# USBINFRTransiever_Photodiod.net
KiCad netlist of a schematic drawn in Altium Designer
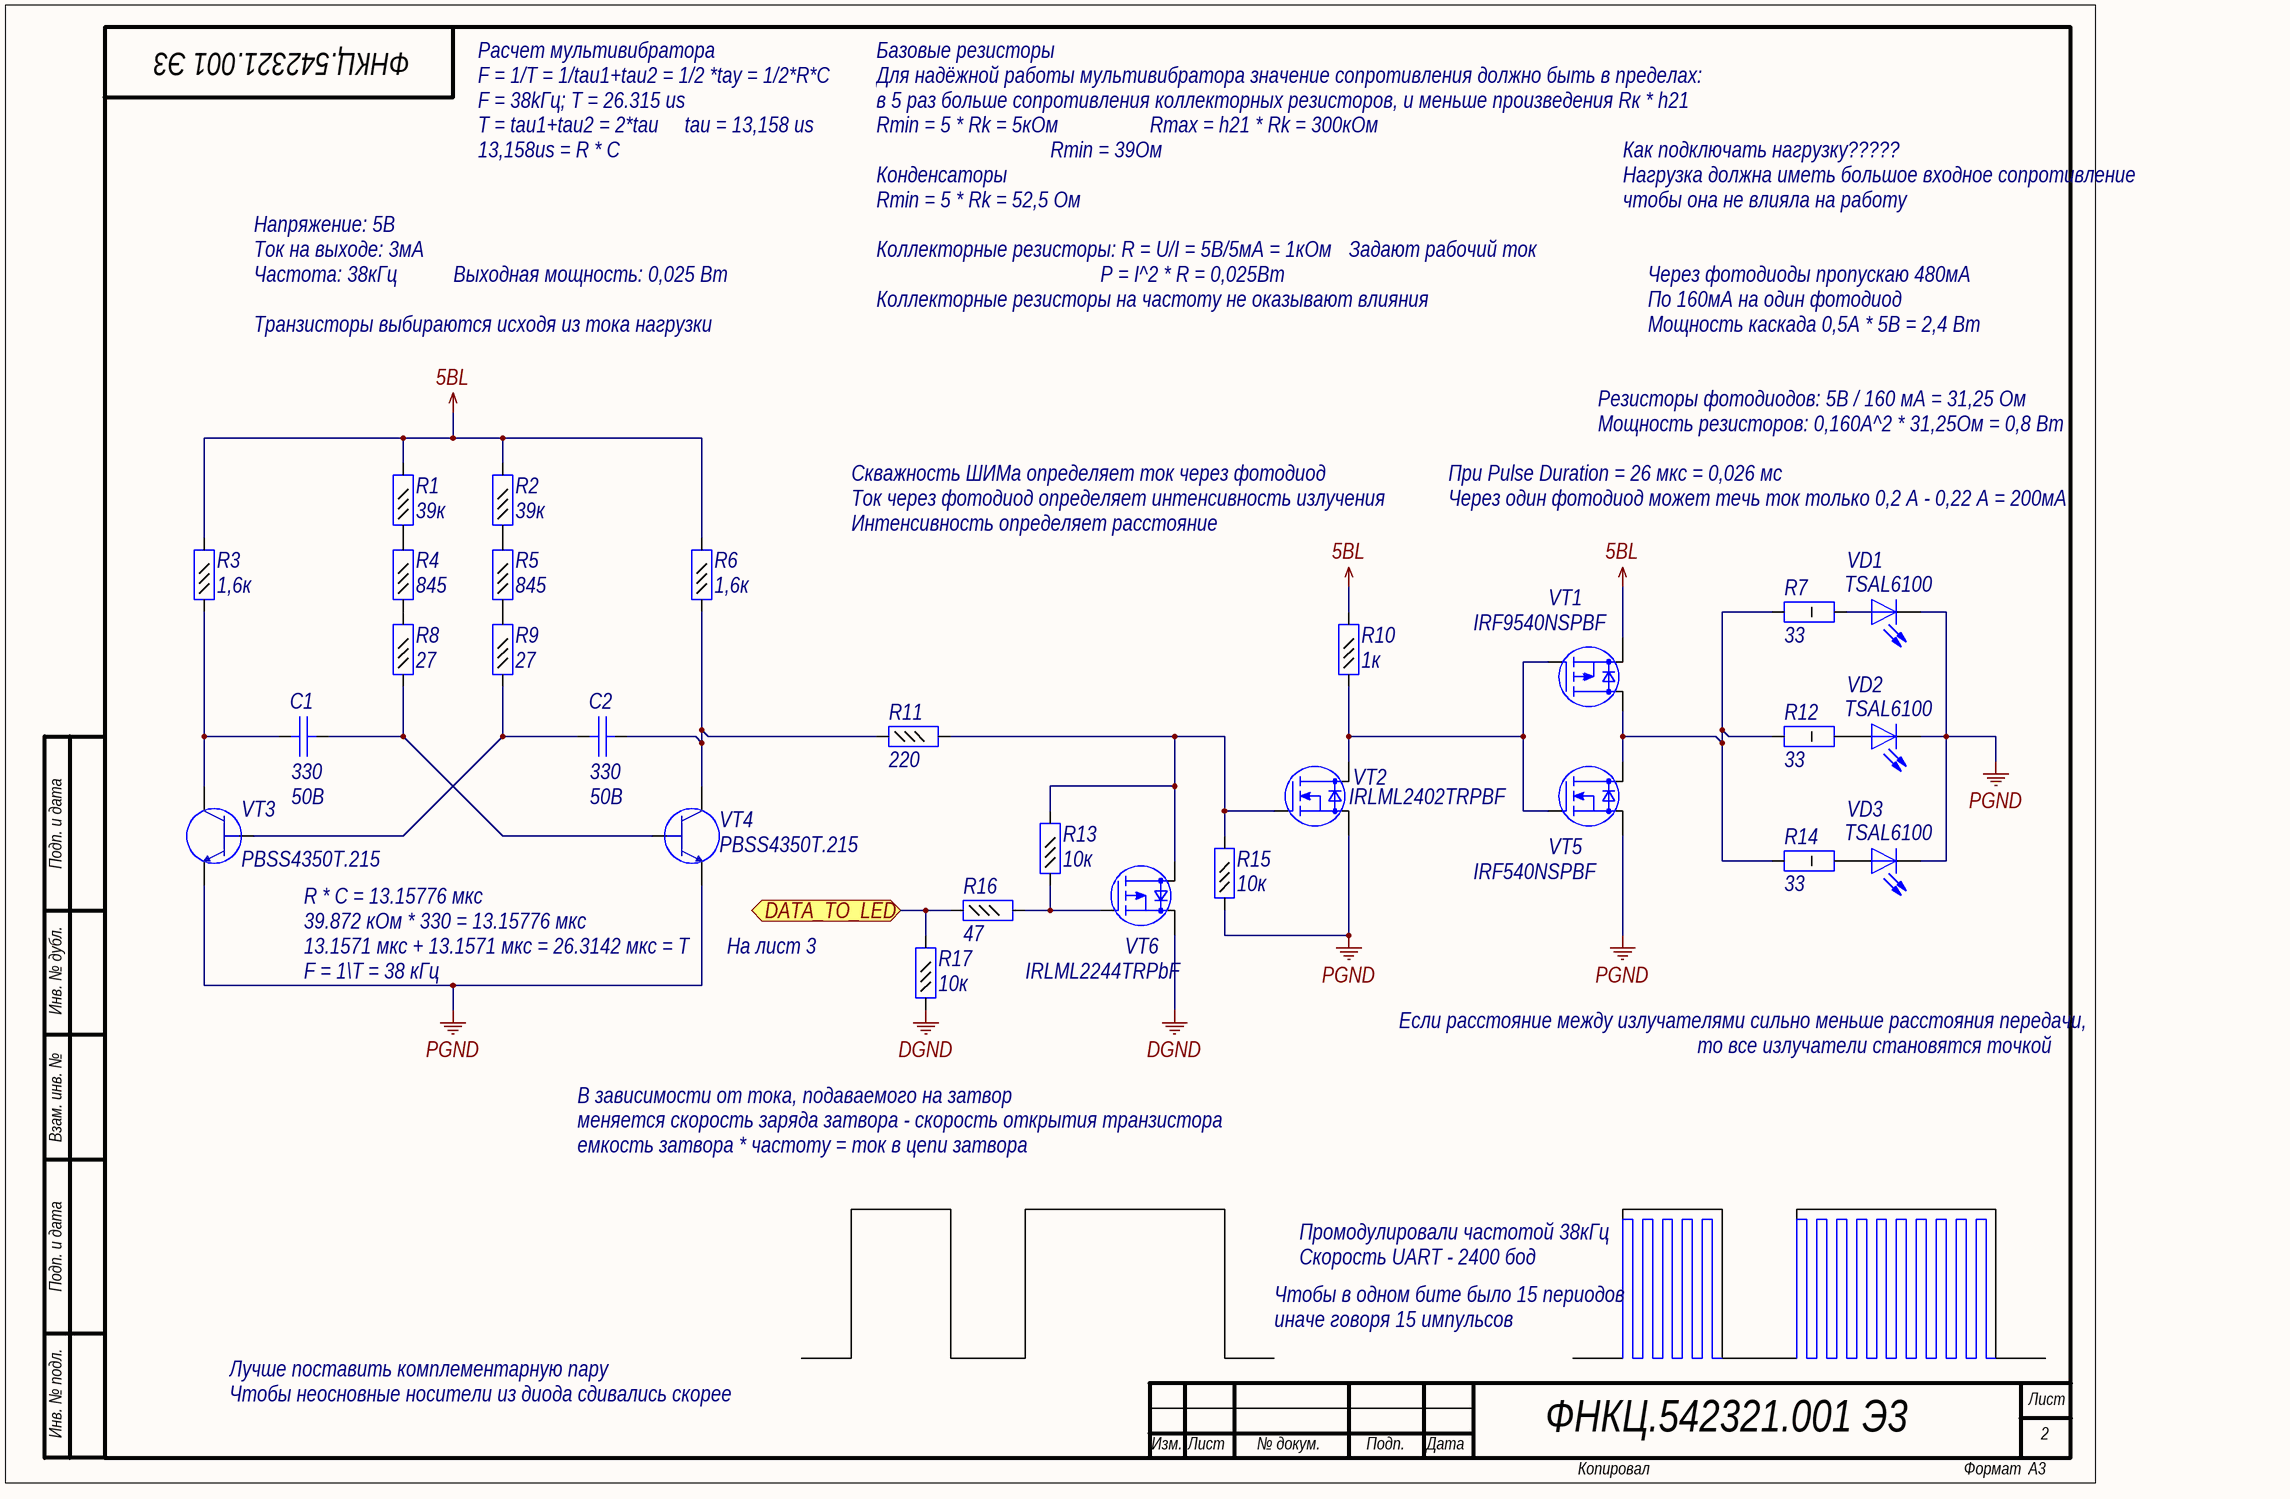
[diagram p0: USBINFRTransiever_Photodiod.SchDoc]

(export (version "E")
  (design (tool "Eeschema 10.0.6"))
  (components
    (comp (ref "C1")
      (value "330")
      (footprint "C0603")
      (description "Конденсатор")
      (fields
        (field (name "VOLTAGE") "50В")
        (field (name "PART NUMBER") "GRM188R71H331KA01D")
        (field (name "Comment") "Capacitor")
      )
      (libsource (lib "MOP44") (part "Capacitor"))
    )
    (comp (ref "C2")
      (value "330")
      (footprint "C0603")
      (description "Конденсатор")
      (fields
        (field (name "VOLTAGE") "50В")
        (field (name "PART NUMBER") "GRM188R71H331KA01D")
        (field (name "Comment") "Capacitor")
      )
      (libsource (lib "MOP44") (part "Capacitor"))
    )
    (comp (ref "R1")
      (value "39к")
      (footprint "R0603")
      (description "Резистор")
      (fields (field (name "PART NUMBER") "RC0603FR-0739KL") (field (name "POWER") "0,062Вт"))
      (libsource (lib "") (part "Resistor_0,062Вт_1"))
    )
    (comp (ref "R2")
      (value "39к")
      (footprint "R0603")
      (description "Резистор")
      (fields (field (name "PART NUMBER") "RC0603FR-0739KL") (field (name "POWER") "0,062Вт"))
      (libsource (lib "") (part "Resistor_0,062Вт_1"))
    )
    (comp (ref "R3")
      (value "1,6к")
      (footprint "R0603")
      (description "Резистор")
      (fields (field (name "PART NUMBER") "RC0603FR-071K6") (field (name "POWER") "0,062Вт"))
      (libsource (lib "") (part "Resistor_0,062Вт_1"))
    )
    (comp (ref "R4")
      (value "845")
      (footprint "R0603")
      (description "Резистор")
      (fields (field (name "PART NUMBER") "RC0603FR-07845RL") (field (name "POWER") "0,062Вт"))
      (libsource (lib "") (part "Resistor_0,062Вт_1"))
    )
    (comp (ref "R5")
      (value "845")
      (footprint "R0603")
      (description "Резистор")
      (fields (field (name "PART NUMBER") "RC0603FR-07845RL") (field (name "POWER") "0,062Вт"))
      (libsource (lib "") (part "Resistor_0,062Вт_1"))
    )
    (comp (ref "R6")
      (value "1,6к")
      (footprint "R0603")
      (description "Резистор")
      (fields (field (name "PART NUMBER") "RC0603FR-071K6") (field (name "POWER") "0,062Вт"))
      (libsource (lib "") (part "Resistor_0,062Вт_1"))
    )
    (comp (ref "R7")
      (value "33")
      (footprint "R2512")
      (description "Резистор")
      (fields (field (name "PART NUMBER") "RC2512FR-0733RL") (field (name "POWER") "1Вт"))
      (libsource (lib "MOP44") (part "Resistor_1Вт"))
    )
    (comp (ref "R8")
      (value "27")
      (footprint "R0603")
      (description "Резистор")
      (fields (field (name "PART NUMBER") "RC0603FR-0727RL") (field (name "POWER") "0,062Вт"))
      (libsource (lib "") (part "Resistor_0,062Вт_1"))
    )
    (comp (ref "R9")
      (value "27")
      (footprint "R0603")
      (description "Резистор")
      (fields (field (name "PART NUMBER") "RC0603FR-0727RL") (field (name "POWER") "0,062Вт"))
      (libsource (lib "") (part "Resistor_0,062Вт_1"))
    )
    (comp (ref "R10")
      (value "1к")
      (footprint "R0603")
      (description "Резистор")
      (fields (field (name "PART NUMBER") "RC0603FR-071KL") (field (name "POWER") "0,062Вт"))
      (libsource (lib "") (part "Resistor_0,062Вт_1"))
    )
    (comp (ref "R11")
      (value "220")
      (footprint "R0603")
      (description "Резистор")
      (fields (field (name "PART NUMBER") "RC0603FR-07220RL") (field (name "POWER") "0,062Вт"))
      (libsource (lib "MOP44") (part "Resistor_0,062Вт"))
    )
    (comp (ref "R12")
      (value "33")
      (footprint "R2512")
      (description "Резистор")
      (fields (field (name "PART NUMBER") "RC2512FR-0733RL") (field (name "POWER") "1Вт"))
      (libsource (lib "MOP44") (part "Resistor_1Вт"))
    )
    (comp (ref "R13")
      (value "10к")
      (footprint "R0603")
      (description "Резистор")
      (fields (field (name "PART NUMBER") "RC0603FR-0710KL") (field (name "POWER") "0,062Вт"))
      (libsource (lib "") (part "Resistor_0,062Вт_1"))
    )
    (comp (ref "R14")
      (value "33")
      (footprint "R2512")
      (description "Резистор")
      (fields (field (name "PART NUMBER") "RC2512FR-0733RL") (field (name "POWER") "1Вт"))
      (libsource (lib "MOP44") (part "Resistor_1Вт"))
    )
    (comp (ref "R15")
      (value "10к")
      (footprint "R0603")
      (description "Резистор")
      (fields (field (name "PART NUMBER") "RC0603FR-0710KL") (field (name "POWER") "0,062Вт"))
      (libsource (lib "") (part "Resistor_0,062Вт_1"))
    )
    (comp (ref "R16")
      (value "47")
      (footprint "R0603")
      (description "Резистор")
      (fields (field (name "PART NUMBER") "RC0603FR-0747RL") (field (name "POWER") "0,062Вт"))
      (libsource (lib "MOP44") (part "Resistor_0,062Вт"))
    )
    (comp (ref "R17")
      (value "10к")
      (footprint "R0603")
      (description "Резистор")
      (fields (field (name "PART NUMBER") "RC0603FR-0710KL") (field (name "POWER") "0,062Вт"))
      (libsource (lib "") (part "Resistor_0,062Вт_1"))
    )
    (comp (ref "VD1")
      (value "LED")
      (footprint "RADIAL_5MM")
      (description "Светодиод")
      (fields (field (name "PART NUMBER") "TSAL6100"))
      (libsource (lib "MOP44") (part "LED"))
    )
    (comp (ref "VD2")
      (value "LED")
      (footprint "RADIAL_5MM")
      (description "Светодиод")
      (fields (field (name "PART NUMBER") "TSAL6100"))
      (libsource (lib "MOP44") (part "LED"))
    )
    (comp (ref "VD3")
      (value "LED")
      (footprint "RADIAL_5MM")
      (description "Светодиод")
      (fields (field (name "PART NUMBER") "TSAL6100"))
      (libsource (lib "MOP44") (part "LED"))
    )
    (comp (ref "VT1")
      (value "P-MOSFET")
      (footprint "D2PAK")
      (description "N-MOSFET")
      (fields
        (field (name "PART NUMBER") "IRF9540NSPBF")
        (field (name "MANUFACTURER") "International Rectifier")
      )
      (libsource (lib "MOP44") (part "P-MOSFET"))
    )
    (comp (ref "VT2")
      (value "N-MOSFET")
      (footprint "SOT23-3")
      (fields
        (field (name "PART NUMBER") "IRLML2402TRPBF")
        (field (name "MANUFACTURER") "International Rectifier")
      )
      (libsource (lib "MOP44") (part "N-MOSFET"))
    )
    (comp (ref "VT3")
      (value "BJT NPN")
      (footprint "SOT23-3")
      (fields (field (name "POWER") "0,48Вт") (field (name "PART NUMBER") "PBSS4350T.215"))
      (libsource (lib "MOP44") (part "BJT NPN"))
    )
    (comp (ref "VT4")
      (value "BJT NPN")
      (footprint "SOT23-3")
      (fields (field (name "POWER") "0,48Вт") (field (name "PART NUMBER") "PBSS4350T.215"))
      (libsource (lib "MOP44") (part "BJT NPN"))
    )
    (comp (ref "VT5")
      (value "N-MOSFET")
      (footprint "D2PAK")
      (fields
        (field (name "PART NUMBER") "IRF540NSPBF")
        (field (name "MANUFACTURER") "International Rectifier")
      )
      (libsource (lib "MOP44") (part "N-MOSFET"))
    )
    (comp (ref "VT6")
      (value "P-MOSFET")
      (footprint "SOT23-3")
      (description "N-MOSFET")
      (fields
        (field (name "PART NUMBER") "IRLML2244TRPbF")
        (field (name "MANUFACTURER") "International Rectifier")
      )
      (libsource (lib "MOP44") (part "P-MOSFET"))
    )
  )
  (nets
    (net (code "1") (name "/DATA_TO_LED") (class "Default")
      (node (ref "R16") (pin "1") (pinfunction "1_1") (pintype "passive"))
      (node (ref "R17") (pin "2") (pinfunction "2_2") (pintype "passive"))
    )
    (net (code "2") (name "5ВL") (class "Default")
      (node (ref "R1") (pin "2") (pinfunction "2_2") (pintype "passive"))
      (node (ref "R10") (pin "2") (pinfunction "2_2") (pintype "passive"))
      (node (ref "R2") (pin "2") (pinfunction "2_2") (pintype "passive"))
      (node (ref "R3") (pin "2") (pinfunction "2_2") (pintype "passive"))
      (node (ref "R6") (pin "2") (pinfunction "2_2") (pintype "passive"))
      (node (ref "VT1") (pin "2") (pinfunction "S_2") (pintype "passive"))
    )
    (net (code "3") (name "DGND") (class "Default")
      (node (ref "R17") (pin "1") (pinfunction "1_1") (pintype "passive"))
      (node (ref "VT6") (pin "2") (pinfunction "S_2") (pintype "passive"))
    )
    (net (code "4") (name "Net-(C1-Pad1)") (class "Default")
      (node (ref "C1") (pin "1") (pinfunction "1_1") (pintype "passive"))
      (node (ref "R3") (pin "1") (pinfunction "1_1") (pintype "passive"))
      (node (ref "VT3") (pin "3") (pinfunction "3_3") (pintype "passive"))
    )
    (net (code "5") (name "Net-(C1-Pad2)") (class "Default")
      (node (ref "C1") (pin "2") (pinfunction "2_2") (pintype "passive"))
      (node (ref "R8") (pin "1") (pinfunction "1_1") (pintype "passive"))
      (node (ref "VT4") (pin "1") (pinfunction "1_1") (pintype "passive"))
    )
    (net (code "6") (name "Net-(C2-Pad1)") (class "Default")
      (node (ref "C2") (pin "1") (pinfunction "1_1") (pintype "passive"))
      (node (ref "R9") (pin "1") (pinfunction "1_1") (pintype "passive"))
      (node (ref "VT3") (pin "1") (pinfunction "1_1") (pintype "passive"))
    )
    (net (code "7") (name "Net-(C2-Pad2)") (class "Default")
      (node (ref "C2") (pin "2") (pinfunction "2_2") (pintype "passive"))
      (node (ref "R11") (pin "1") (pinfunction "1_1") (pintype "passive"))
      (node (ref "R6") (pin "1") (pinfunction "1_1") (pintype "passive"))
      (node (ref "VT4") (pin "3") (pinfunction "3_3") (pintype "passive"))
    )
    (net (code "8") (name "Net-(R1-Pad1)") (class "Default")
      (node (ref "R1") (pin "1") (pinfunction "1_1") (pintype "passive"))
      (node (ref "R4") (pin "2") (pinfunction "2_2") (pintype "passive"))
    )
    (net (code "9") (name "Net-(R2-Pad1)") (class "Default")
      (node (ref "R2") (pin "1") (pinfunction "1_1") (pintype "passive"))
      (node (ref "R5") (pin "2") (pinfunction "2_2") (pintype "passive"))
    )
    (net (code "10") (name "Net-(R4-Pad1)") (class "Default")
      (node (ref "R4") (pin "1") (pinfunction "1_1") (pintype "passive"))
      (node (ref "R8") (pin "2") (pinfunction "2_2") (pintype "passive"))
    )
    (net (code "11") (name "Net-(R5-Pad1)") (class "Default")
      (node (ref "R5") (pin "1") (pinfunction "1_1") (pintype "passive"))
      (node (ref "R9") (pin "2") (pinfunction "2_2") (pintype "passive"))
    )
    (net (code "12") (name "Net-(R7-5)") (class "Default")
      (node (ref "R7") (pin "2") (pinfunction "5_2") (pintype "passive"))
      (node (ref "VD1") (pin "2") (pinfunction "A_2") (pintype "passive"))
    )
    (net (code "13") (name "Net-(R12-5)") (class "Default")
      (node (ref "R12") (pin "2") (pinfunction "5_2") (pintype "passive"))
      (node (ref "VD2") (pin "2") (pinfunction "A_2") (pintype "passive"))
    )
    (net (code "14") (name "Net-(R14-5)") (class "Default")
      (node (ref "R14") (pin "2") (pinfunction "5_2") (pintype "passive"))
      (node (ref "VD3") (pin "2") (pinfunction "A_2") (pintype "passive"))
    )
    (net (code "15") (name "Net-(VT1-D)") (class "Default")
      (node (ref "R12") (pin "1") (pinfunction "1_1") (pintype "passive"))
      (node (ref "R14") (pin "1") (pinfunction "1_1") (pintype "passive"))
      (node (ref "R7") (pin "1") (pinfunction "1_1") (pintype "passive"))
      (node (ref "VT1") (pin "3") (pinfunction "D_3") (pintype "passive"))
      (node (ref "VT5") (pin "3") (pinfunction "D_3") (pintype "passive"))
    )
    (net (code "16") (name "Net-(VT1-G)") (class "Default")
      (node (ref "R10") (pin "1") (pinfunction "1_1") (pintype "passive"))
      (node (ref "VT1") (pin "1") (pinfunction "G_1") (pintype "passive"))
      (node (ref "VT2") (pin "3") (pinfunction "D_3") (pintype "passive"))
      (node (ref "VT5") (pin "1") (pinfunction "G_1") (pintype "passive"))
    )
    (net (code "17") (name "Net-(VT2-G)") (class "Default")
      (node (ref "R11") (pin "2") (pinfunction "2_2") (pintype "passive"))
      (node (ref "R13") (pin "2") (pinfunction "2_2") (pintype "passive"))
      (node (ref "R15") (pin "2") (pinfunction "2_2") (pintype "passive"))
      (node (ref "VT2") (pin "1") (pinfunction "G_1") (pintype "passive"))
      (node (ref "VT6") (pin "3") (pinfunction "D_3") (pintype "passive"))
    )
    (net (code "18") (name "Net-(VT6-G)") (class "Default")
      (node (ref "R13") (pin "1") (pinfunction "1_1") (pintype "passive"))
      (node (ref "R16") (pin "2") (pinfunction "2_2") (pintype "passive"))
      (node (ref "VT6") (pin "1") (pinfunction "G_1") (pintype "passive"))
    )
    (net (code "19") (name "PGND") (class "Default")
      (node (ref "R15") (pin "1") (pinfunction "1_1") (pintype "passive"))
      (node (ref "VD1") (pin "1") (pinfunction "K_1") (pintype "passive"))
      (node (ref "VD2") (pin "1") (pinfunction "K_1") (pintype "passive"))
      (node (ref "VD3") (pin "1") (pinfunction "K_1") (pintype "passive"))
      (node (ref "VT2") (pin "2") (pinfunction "S_2") (pintype "passive"))
      (node (ref "VT3") (pin "2") (pinfunction "2_2") (pintype "passive"))
      (node (ref "VT4") (pin "2") (pinfunction "2_2") (pintype "passive"))
      (node (ref "VT5") (pin "2") (pinfunction "S_2") (pintype "passive"))
    )
  )
)
